# Ardev_version_3.net
KiCad netlist of a schematic drawn in EAGLE
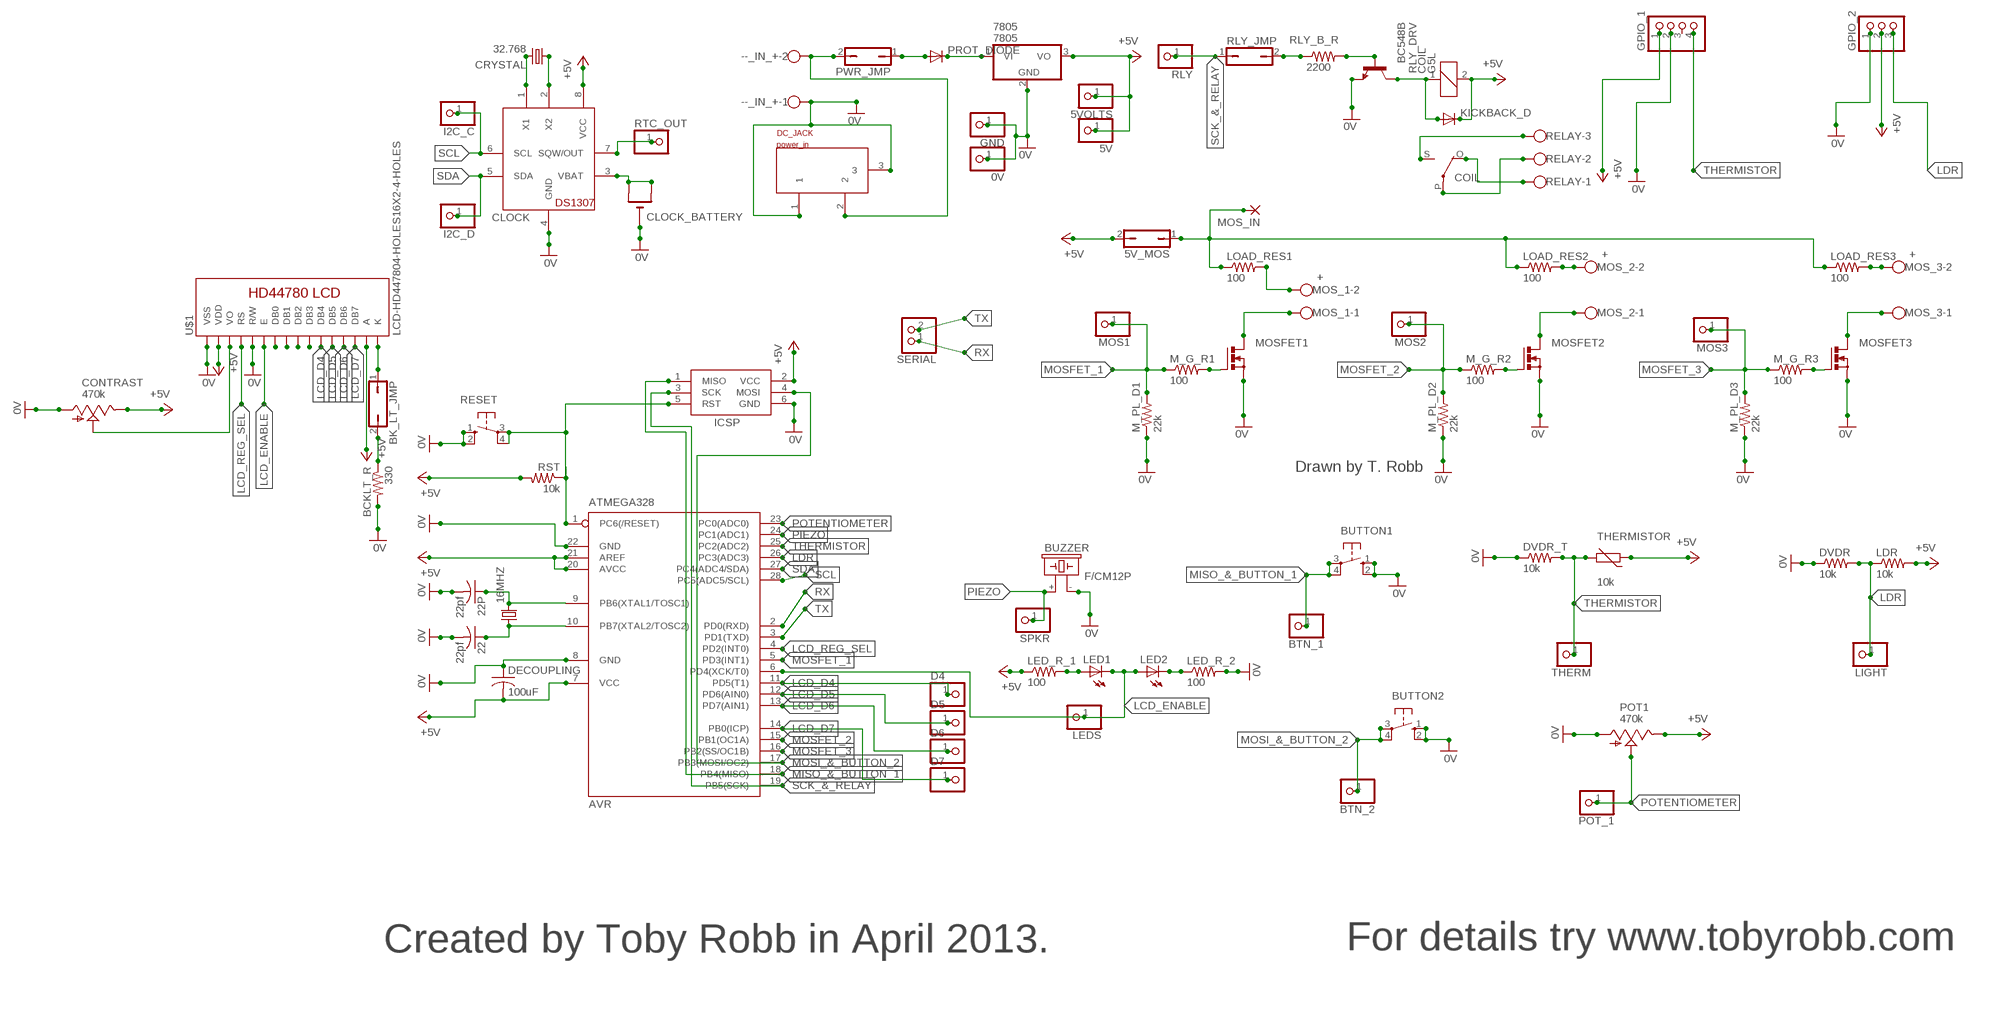
[diagram p0: schematic, sheet 1, part 1 of 2]
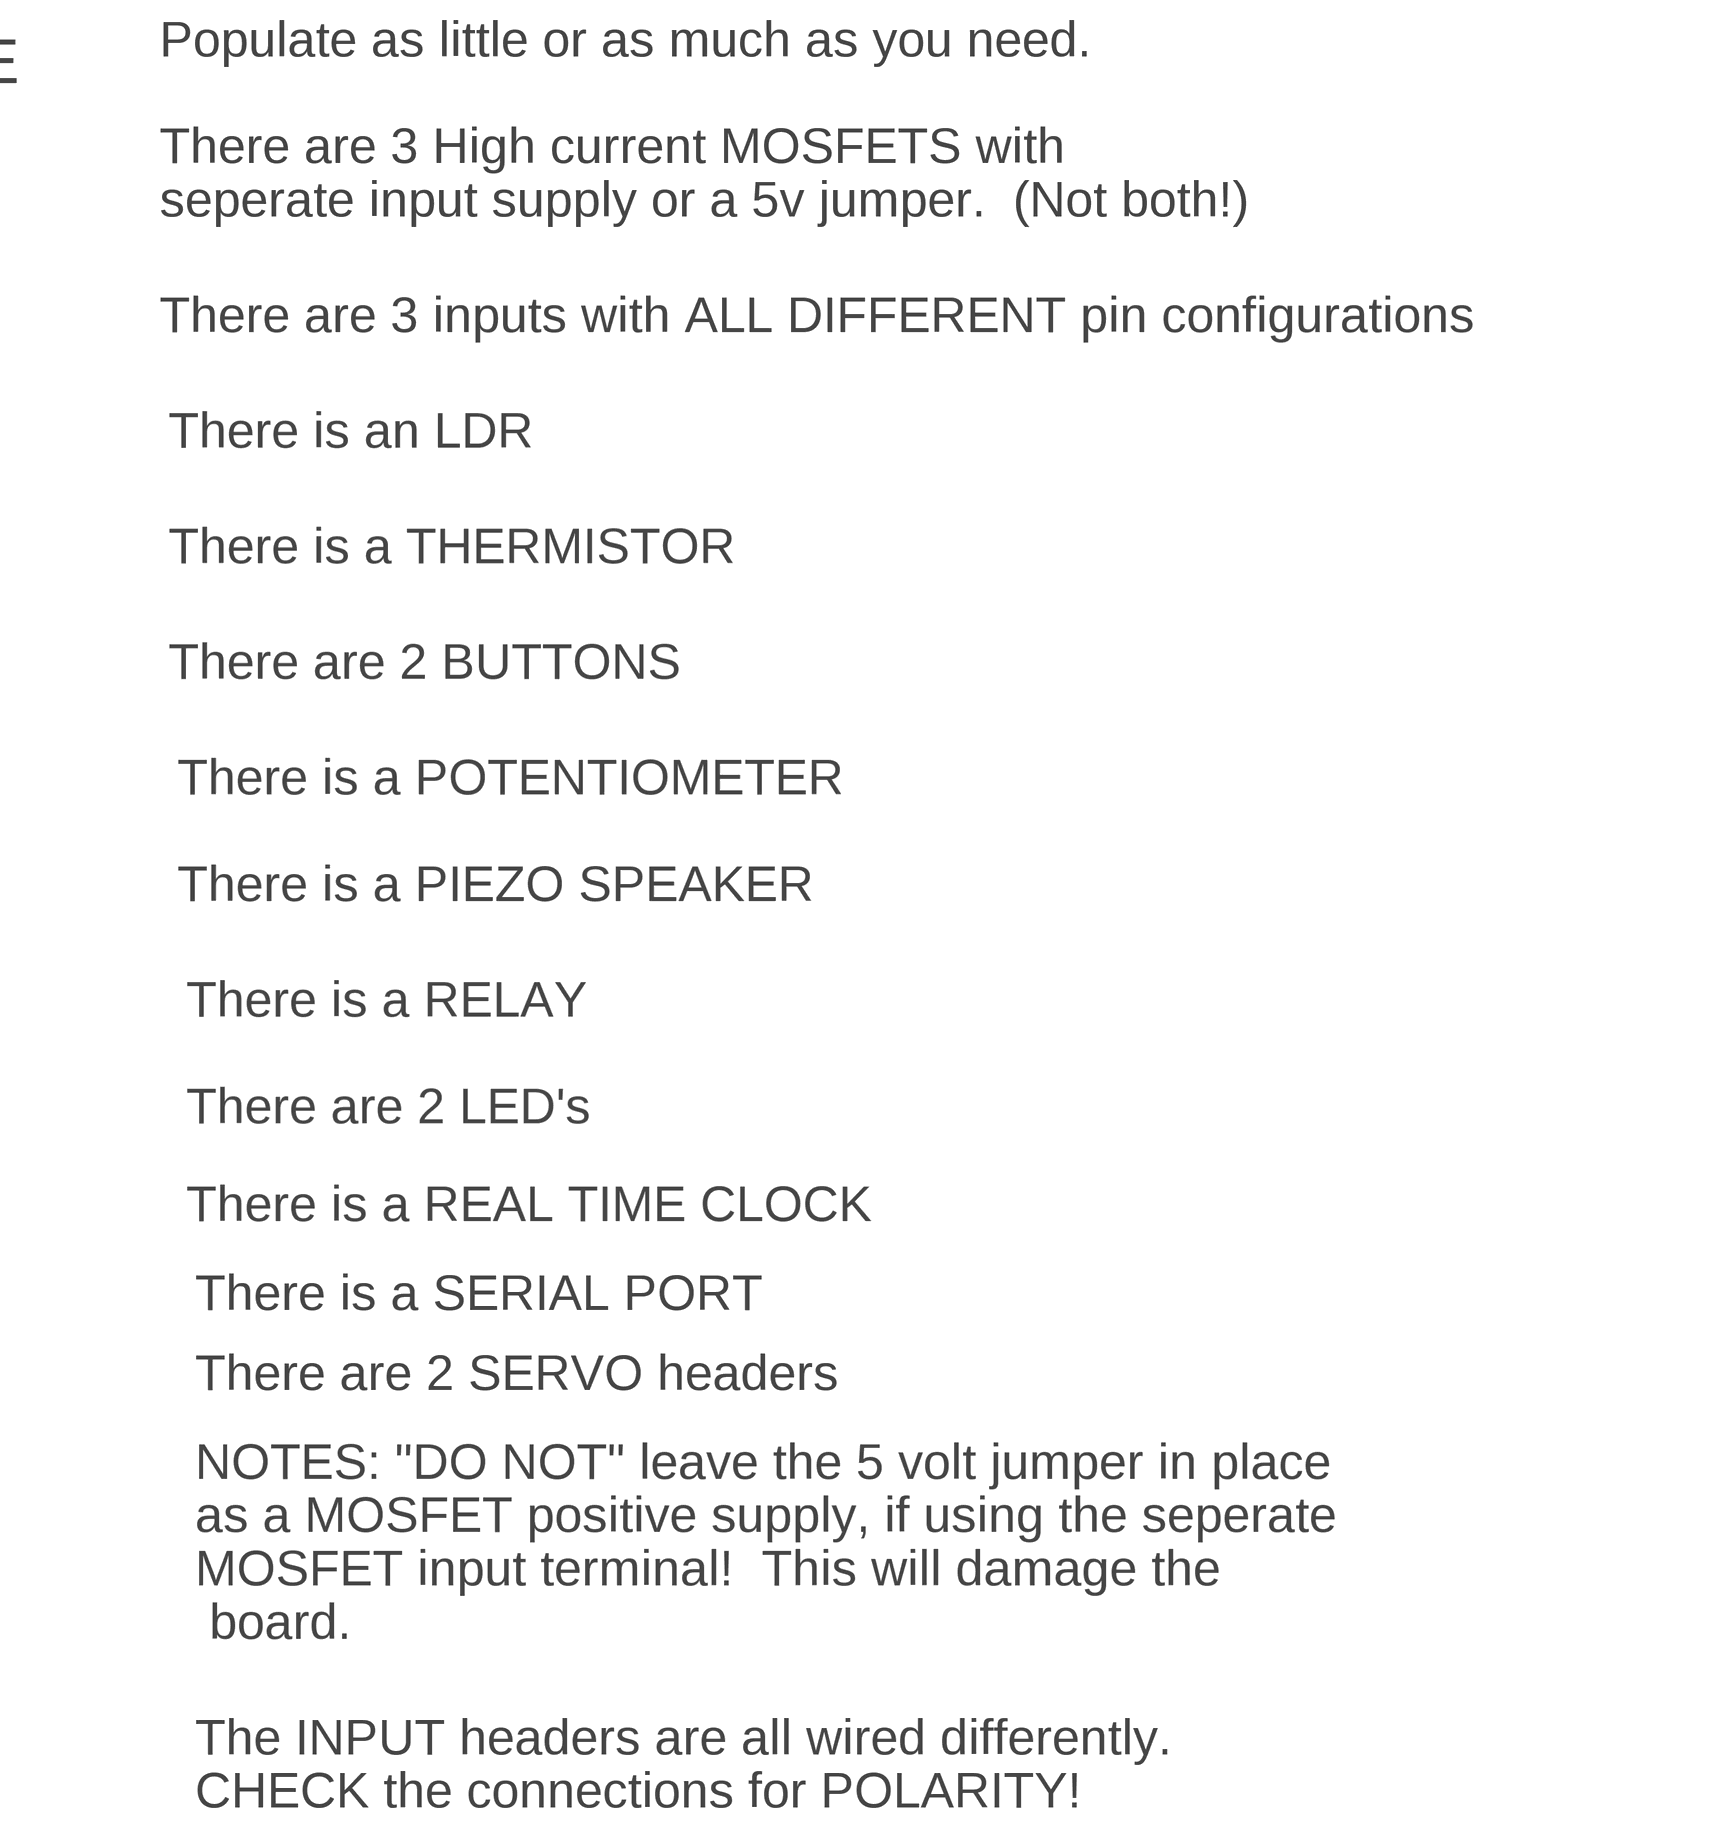
[diagram p1: schematic, sheet 1, part 2 of 2]

(export (version "E")
  (design (tool "Eeschema 10.0.6"))
  (components
    (comp (ref "--_IN_+")
      (value "W237-102")
      (footprint "eagle-import:W237-102")
      (fields (field (name "MPN") "237-102"))
      (libsource (lib "eagle-import") (part "W237-102"))
    )
    (comp (ref "0V")
      (value "PINHD-1X1")
      (footprint "eagle-import:1X01")
      (libsource (lib "eagle-import") (part "PINHD-1X1"))
    )
    (comp (ref "5V")
      (value "PINHD-1X1")
      (footprint "eagle-import:1X01")
      (libsource (lib "eagle-import") (part "PINHD-1X1"))
    )
    (comp (ref "5VOLTS")
      (value "PINHD-1X1")
      (footprint "eagle-import:1X01")
      (libsource (lib "eagle-import") (part "PINHD-1X1"))
    )
    (comp (ref "5V_MOS")
      (value "JP1Q")
      (footprint "eagle-import:JP1")
      (libsource (lib "eagle-import") (part "JP1Q"))
    )
    (comp (ref "16MHZ")
      (value "CRYSTALHC49U-V")
      (footprint "eagle-import:HC49U-V")
      (libsource (lib "eagle-import") (part "CRYSTALHC49U-V"))
    )
    (comp (ref "22")
      (value "22pf")
      (footprint "eagle-import:C025-050X050")
      (libsource (lib "eagle-import") (part "C-US025-050X050"))
    )
    (comp (ref "22P")
      (value "22pf")
      (footprint "eagle-import:C025-050X050")
      (libsource (lib "eagle-import") (part "C-US025-050X050"))
    )
    (comp (ref "7805")
      (value "7805")
      (footprint "eagle-import:TO220V")
      (libsource (lib "eagle-import") (part "78TV05"))
    )
    (comp (ref "AVR")
      (value "ATMEGA328")
      (footprint "eagle-import:DIL28-3")
      (libsource (lib "eagle-import") (part "MEGA8-P"))
    )
    (comp (ref "BCKLT_R")
      (value "330")
      (footprint "eagle-import:0309V")
      (libsource (lib "eagle-import") (part "R-US_0309/V"))
    )
    (comp (ref "BK_LT_JMP")
      (value "JP1Q")
      (footprint "eagle-import:JP1")
      (libsource (lib "eagle-import") (part "JP1Q"))
    )
    (comp (ref "BTN_1")
      (value "PINHD-1X1")
      (footprint "eagle-import:1X01")
      (libsource (lib "eagle-import") (part "PINHD-1X1"))
    )
    (comp (ref "BTN_2")
      (value "PINHD-1X1")
      (footprint "eagle-import:1X01")
      (libsource (lib "eagle-import") (part "PINHD-1X1"))
    )
    (comp (ref "BUTTON1")
      (value "10-XX")
      (footprint "eagle-import:B3F-10XX")
      (fields (field (name "MPN") "B3F-1000"))
      (libsource (lib "eagle-import") (part "10-XX"))
    )
    (comp (ref "BUTTON2")
      (value "10-XX")
      (footprint "eagle-import:B3F-10XX")
      (fields (field (name "MPN") "B3F-1000"))
      (libsource (lib "eagle-import") (part "10-XX"))
    )
    (comp (ref "BUZZER")
      (value "F/CM12P")
      (footprint "eagle-import:F_CM12P")
      (libsource (lib "eagle-import") (part "F/CM12P"))
    )
    (comp (ref "CLOCK")
      (value "DS1307")
      (footprint "eagle-import:DIL08")
      (libsource (lib "eagle-import") (part "DS1307"))
    )
    (comp (ref "CLOCK_BATTERY")
      (value "CR1220THM")
      (footprint "eagle-import:CR1220-THM")
      (libsource (lib "eagle-import") (part "CR1220THM"))
    )
    (comp (ref "COIL")
      (value "G5L")
      (footprint "eagle-import:G5LE")
      (libsource (lib "eagle-import") (part "G5L"))
    )
    (comp (ref "CONTRAST")
      (value "470k")
      (footprint "eagle-import:CA6V")
      (libsource (lib "eagle-import") (part "TRIM_US-CA6V"))
    )
    (comp (ref "CRYSTAL")
      (value "32.768")
      (footprint "eagle-import:TC26H")
      (libsource (lib "eagle-import") (part "CRYSTALTC26H"))
    )
    (comp (ref "D4")
      (value "PINHD-1X1")
      (footprint "eagle-import:1X01")
      (libsource (lib "eagle-import") (part "PINHD-1X1"))
    )
    (comp (ref "D5")
      (value "PINHD-1X1")
      (footprint "eagle-import:1X01")
      (libsource (lib "eagle-import") (part "PINHD-1X1"))
    )
    (comp (ref "D6")
      (value "PINHD-1X1")
      (footprint "eagle-import:1X01")
      (libsource (lib "eagle-import") (part "PINHD-1X1"))
    )
    (comp (ref "D7")
      (value "PINHD-1X1")
      (footprint "eagle-import:1X01")
      (libsource (lib "eagle-import") (part "PINHD-1X1"))
    )
    (comp (ref "DC_JACK")
      (value "power_in")
      (footprint "eagle-import:SMARTPRJ_POWERSUPPLY_DC-21MM")
      (libsource (lib "eagle-import") (part "SMARTPRJ_POWERSUPPLY_DC21MMX"))
    )
    (comp (ref "DECOUPLING")
      (value "100uF")
      (footprint "eagle-import:C025-050X050")
      (libsource (lib "eagle-import") (part "C-US025-050X050"))
    )
    (comp (ref "DVDR")
      (value "10k")
      (footprint "eagle-import:0309V")
      (libsource (lib "eagle-import") (part "R-US_0309/V"))
    )
    (comp (ref "DVDR_T")
      (value "10k")
      (footprint "eagle-import:0309V")
      (libsource (lib "eagle-import") (part "R-US_0309/V"))
    )
    (comp (ref "GND")
      (value "PINHD-1X1")
      (footprint "eagle-import:1X01")
      (libsource (lib "eagle-import") (part "PINHD-1X1"))
    )
    (comp (ref "GPIO_1")
      (value "PINHD-1X4")
      (footprint "eagle-import:1X04")
      (libsource (lib "eagle-import") (part "PINHD-1X4"))
    )
    (comp (ref "GPIO_2")
      (value "PINHD-1X3")
      (footprint "eagle-import:1X03")
      (libsource (lib "eagle-import") (part "PINHD-1X3"))
    )
    (comp (ref "I2C_C")
      (value "PINHD-1X1")
      (footprint "eagle-import:1X01")
      (libsource (lib "eagle-import") (part "PINHD-1X1"))
    )
    (comp (ref "I2C_D")
      (value "PINHD-1X1")
      (footprint "eagle-import:1X01")
      (libsource (lib "eagle-import") (part "PINHD-1X1"))
    )
    (comp (ref "ICSP")
      (value "AVRISP-6")
      (footprint "eagle-import:AVRISP")
      (libsource (lib "eagle-import") (part "AVRISP-6"))
    )
    (comp (ref "KICKBACK_D")
      (value "DIODE-D-7.5")
      (footprint "eagle-import:D-7.5")
      (libsource (lib "eagle-import") (part "DIODE-D-7.5"))
    )
    (comp (ref "LDR")
      (value "10k")
      (footprint "eagle-import:0309V")
      (libsource (lib "eagle-import") (part "R-US_0309/V"))
    )
    (comp (ref "LED1")
      (value "LED5MM")
      (footprint "eagle-import:LED5MM")
      (libsource (lib "eagle-import") (part "LED5MM"))
    )
    (comp (ref "LED2")
      (value "LED5MM")
      (footprint "eagle-import:LED5MM")
      (libsource (lib "eagle-import") (part "LED5MM"))
    )
    (comp (ref "LEDS")
      (value "PINHD-1X1")
      (footprint "eagle-import:1X01")
      (libsource (lib "eagle-import") (part "PINHD-1X1"))
    )
    (comp (ref "LED_R_1")
      (value "100")
      (footprint "eagle-import:0207_2V")
      (libsource (lib "eagle-import") (part "R-US_0207/2V"))
    )
    (comp (ref "LED_R_2")
      (value "100")
      (footprint "eagle-import:0207_2V")
      (libsource (lib "eagle-import") (part "R-US_0207/2V"))
    )
    (comp (ref "LIGHT")
      (value "PINHD-1X1")
      (footprint "eagle-import:1X01")
      (libsource (lib "eagle-import") (part "PINHD-1X1"))
    )
    (comp (ref "LOAD_RES1")
      (value "100")
      (footprint "eagle-import:0309V")
      (libsource (lib "eagle-import") (part "R-US_0309/V"))
    )
    (comp (ref "LOAD_RES2")
      (value "100")
      (footprint "eagle-import:0309V")
      (libsource (lib "eagle-import") (part "R-US_0309/V"))
    )
    (comp (ref "LOAD_RES3")
      (value "100")
      (footprint "eagle-import:0309V")
      (libsource (lib "eagle-import") (part "R-US_0309/V"))
    )
    (comp (ref "MOS1")
      (value "PINHD-1X1")
      (footprint "eagle-import:1X01")
      (libsource (lib "eagle-import") (part "PINHD-1X1"))
    )
    (comp (ref "MOS2")
      (value "PINHD-1X1")
      (footprint "eagle-import:1X01")
      (libsource (lib "eagle-import") (part "PINHD-1X1"))
    )
    (comp (ref "MOS3")
      (value "PINHD-1X1")
      (footprint "eagle-import:1X01")
      (libsource (lib "eagle-import") (part "PINHD-1X1"))
    )
    (comp (ref "MOSFET1")
      (value "IRF512")
      (footprint "eagle-import:TO220BV")
      (libsource (lib "eagle-import") (part "IRF512"))
    )
    (comp (ref "MOSFET2")
      (value "IRF512")
      (footprint "eagle-import:TO220BV")
      (libsource (lib "eagle-import") (part "IRF512"))
    )
    (comp (ref "MOSFET3")
      (value "IRF512")
      (footprint "eagle-import:TO220BV")
      (libsource (lib "eagle-import") (part "IRF512"))
    )
    (comp (ref "MOS_1")
      (value "+")
      (footprint "eagle-import:W237-102")
      (fields (field (name "MPN") "237-102"))
      (libsource (lib "eagle-import") (part "W237-102"))
    )
    (comp (ref "MOS_2")
      (value "+")
      (footprint "eagle-import:W237-102")
      (fields (field (name "MPN") "237-102"))
      (libsource (lib "eagle-import") (part "W237-102"))
    )
    (comp (ref "MOS_3")
      (value "+")
      (footprint "eagle-import:W237-102")
      (fields (field (name "MPN") "237-102"))
      (libsource (lib "eagle-import") (part "W237-102"))
    )
    (comp (ref "MOS_IN")
      (value "3,17/1,3")
      (footprint "eagle-import:3,17_1,3")
      (libsource (lib "eagle-import") (part "3,17/1,3"))
    )
    (comp (ref "M_G_R1")
      (value "100")
      (footprint "eagle-import:0309V")
      (libsource (lib "eagle-import") (part "R-US_0309/V"))
    )
    (comp (ref "M_G_R2")
      (value "100")
      (footprint "eagle-import:0309V")
      (libsource (lib "eagle-import") (part "R-US_0309/V"))
    )
    (comp (ref "M_G_R3")
      (value "100")
      (footprint "eagle-import:0309V")
      (libsource (lib "eagle-import") (part "R-US_0309/V"))
    )
    (comp (ref "M_PL_D1")
      (value "22k")
      (footprint "eagle-import:0309V")
      (libsource (lib "eagle-import") (part "R-US_0309/V"))
    )
    (comp (ref "M_PL_D2")
      (value "22k")
      (footprint "eagle-import:0309V")
      (libsource (lib "eagle-import") (part "R-US_0309/V"))
    )
    (comp (ref "M_PL_D3")
      (value "22k")
      (footprint "eagle-import:0309V")
      (libsource (lib "eagle-import") (part "R-US_0309/V"))
    )
    (comp (ref "POT1")
      (value "470k")
      (footprint "eagle-import:CA6V")
      (libsource (lib "eagle-import") (part "TRIM_US-CA6V"))
    )
    (comp (ref "POT_1")
      (value "PINHD-1X1")
      (footprint "eagle-import:1X01")
      (libsource (lib "eagle-import") (part "PINHD-1X1"))
    )
    (comp (ref "PROT_DIODE")
      (value "DIODE-D-7.5")
      (footprint "eagle-import:D-7.5")
      (libsource (lib "eagle-import") (part "DIODE-D-7.5"))
    )
    (comp (ref "PWR_JMP")
      (value "JP1Q")
      (footprint "eagle-import:JP1")
      (libsource (lib "eagle-import") (part "JP1Q"))
    )
    (comp (ref "RELAY")
      (value "W237-103")
      (footprint "eagle-import:W237-103")
      (fields (field (name "MPN") "237-103"))
      (libsource (lib "eagle-import") (part "W237-103"))
    )
    (comp (ref "RESET")
      (value "10-XX")
      (footprint "eagle-import:B3F-10XX")
      (fields (field (name "MPN") "B3F-1000"))
      (libsource (lib "eagle-import") (part "10-XX"))
    )
    (comp (ref "RLY")
      (value "PINHD-1X1")
      (footprint "eagle-import:1X01")
      (libsource (lib "eagle-import") (part "PINHD-1X1"))
    )
    (comp (ref "RLY_B_R")
      (value "2200")
      (footprint "eagle-import:0309V")
      (libsource (lib "eagle-import") (part "R-US_0309/V"))
    )
    (comp (ref "RLY_DRV")
      (value "BC548B")
      (footprint "eagle-import:TO92-EBC")
      (libsource (lib "eagle-import") (part "BC548B"))
    )
    (comp (ref "RLY_JMP")
      (value "JP1Q")
      (footprint "eagle-import:JP1")
      (libsource (lib "eagle-import") (part "JP1Q"))
    )
    (comp (ref "RST")
      (value "10k")
      (footprint "eagle-import:0309V")
      (libsource (lib "eagle-import") (part "R-US_0309/V"))
    )
    (comp (ref "RTC_OUT")
      (value "PINHD-1X1")
      (footprint "eagle-import:1X01")
      (libsource (lib "eagle-import") (part "PINHD-1X1"))
    )
    (comp (ref "SERIAL")
      (value "PINHD-1X2")
      (footprint "eagle-import:1X02")
      (libsource (lib "eagle-import") (part "PINHD-1X2"))
    )
    (comp (ref "SPKR")
      (value "PINHD-1X1")
      (footprint "eagle-import:1X01")
      (libsource (lib "eagle-import") (part "PINHD-1X1"))
    )
    (comp (ref "THERM")
      (value "PINHD-1X1")
      (footprint "eagle-import:1X01")
      (libsource (lib "eagle-import") (part "PINHD-1X1"))
    )
    (comp (ref "THERMISTOR")
      (value "10k")
      (footprint "eagle-import:RS-2,5")
      (libsource (lib "eagle-import") (part "THERMISTOR_R-2,5"))
    )
    (comp (ref "U$1")
      (value "LCD-HD447804-HOLES16X2-4-HOLES")
      (footprint "eagle-import:LCD-16X2-4HOLES")
      (libsource (lib "eagle-import") (part "LCD-HD4478016X2-4-HOLES4-HOLES"))
    )
  )
  (nets
    (net (code "1") (name "+5V") (class "Default")
      (node (ref "5V") (pin "1") (pinfunction "1_1") (pintype "passive"))
      (node (ref "5VOLTS") (pin "1") (pinfunction "1_1") (pintype "passive"))
      (node (ref "5V_MOS") (pin "2") (pinfunction "2_2") (pintype "passive"))
      (node (ref "7805") (pin "3") (pinfunction "VO_3") (pintype "passive"))
      (node (ref "AVR") (pin "20") (pinfunction "AVCC_20") (pintype "power_in"))
      (node (ref "AVR") (pin "21") (pinfunction "AREF_21") (pintype "passive"))
      (node (ref "AVR") (pin "7") (pinfunction "VCC_7") (pintype "power_in"))
      (node (ref "CLOCK") (pin "8") (pinfunction "VCC_8") (pintype "power_in"))
      (node (ref "COIL") (pin "2") (pinfunction "2_2") (pintype "passive"))
      (node (ref "CONTRAST") (pin "E") (pinfunction "E_E") (pintype "passive"))
      (node (ref "DECOUPLING") (pin "2") (pinfunction "2_2") (pintype "passive"))
      (node (ref "GPIO_1") (pin "1") (pinfunction "1_1") (pintype "passive"))
      (node (ref "GPIO_2") (pin "2") (pinfunction "2_2") (pintype "passive"))
      (node (ref "ICSP") (pin "2") (pinfunction "VCC_2") (pintype "power_in"))
      (node (ref "KICKBACK_D") (pin "C") (pinfunction "C_C") (pintype "passive"))
      (node (ref "LDR") (pin "2") (pinfunction "2_2") (pintype "passive"))
      (node (ref "LED_R_1") (pin "1") (pinfunction "1_1") (pintype "passive"))
      (node (ref "POT1") (pin "E") (pinfunction "E_E") (pintype "passive"))
      (node (ref "RST") (pin "2") (pinfunction "2_2") (pintype "passive"))
      (node (ref "THERMISTOR") (pin "1") (pinfunction "1_1") (pintype "passive"))
      (node (ref "U$1") (pin "15") (pinfunction "A_15") (pintype "power_in"))
      (node (ref "U$1") (pin "2") (pinfunction "VDD_2") (pintype "power_in"))
    )
    (net (code "2") (name "0V") (class "Default")
      (node (ref "--_IN_+") (pin "1") (pinfunction "KL_1") (pintype "passive"))
      (node (ref "0V") (pin "1") (pinfunction "1_1") (pintype "passive"))
      (node (ref "22") (pin "2") (pinfunction "2_2") (pintype "passive"))
      (node (ref "22P") (pin "2") (pinfunction "2_2") (pintype "passive"))
      (node (ref "7805") (pin "2") (pinfunction "GND_2") (pintype "passive"))
      (node (ref "AVR") (pin "22") (pinfunction "GND_22") (pintype "power_in"))
      (node (ref "AVR") (pin "8") (pinfunction "GND_8") (pintype "power_in"))
      (node (ref "BCKLT_R") (pin "2") (pinfunction "2_2") (pintype "passive"))
      (node (ref "BUTTON1") (pin "1") (pinfunction "S_1") (pintype "passive"))
      (node (ref "BUTTON1") (pin "2") (pinfunction "S1_2") (pintype "passive"))
      (node (ref "BUTTON2") (pin "1") (pinfunction "S_1") (pintype "passive"))
      (node (ref "BUTTON2") (pin "2") (pinfunction "S1_2") (pintype "passive"))
      (node (ref "BUZZER") (pin "-") (pinfunction "2_-") (pintype "passive"))
      (node (ref "CLOCK") (pin "4") (pinfunction "GND_4") (pintype "power_in"))
      (node (ref "CLOCK_BATTERY") (pin "-") (pinfunction "-_-") (pintype "passive"))
      (node (ref "CONTRAST") (pin "A") (pinfunction "A_A") (pintype "passive"))
      (node (ref "DC_JACK") (pin "1") (pinfunction "1_1") (pintype "power_in"))
      (node (ref "DC_JACK") (pin "3") (pinfunction "3_3") (pintype "power_in"))
      (node (ref "DECOUPLING") (pin "1") (pinfunction "1_1") (pintype "passive"))
      (node (ref "DVDR") (pin "1") (pinfunction "1_1") (pintype "passive"))
      (node (ref "DVDR_T") (pin "1") (pinfunction "1_1") (pintype "passive"))
      (node (ref "GND") (pin "1") (pinfunction "1_1") (pintype "passive"))
      (node (ref "GPIO_1") (pin "2") (pinfunction "2_2") (pintype "passive"))
      (node (ref "GPIO_2") (pin "1") (pinfunction "1_1") (pintype "passive"))
      (node (ref "ICSP") (pin "6") (pinfunction "GND_6") (pintype "power_in"))
      (node (ref "LED_R_2") (pin "2") (pinfunction "2_2") (pintype "passive"))
      (node (ref "MOSFET1") (pin "S") (pinfunction "S_S") (pintype "passive"))
      (node (ref "MOSFET2") (pin "S") (pinfunction "S_S") (pintype "passive"))
      (node (ref "MOSFET3") (pin "S") (pinfunction "S_S") (pintype "passive"))
      (node (ref "M_PL_D1") (pin "1") (pinfunction "1_1") (pintype "passive"))
      (node (ref "M_PL_D2") (pin "1") (pinfunction "1_1") (pintype "passive"))
      (node (ref "M_PL_D3") (pin "1") (pinfunction "1_1") (pintype "passive"))
      (node (ref "POT1") (pin "A") (pinfunction "A_A") (pintype "passive"))
      (node (ref "RESET") (pin "1") (pinfunction "S_1") (pintype "passive"))
      (node (ref "RESET") (pin "2") (pinfunction "S1_2") (pintype "passive"))
      (node (ref "RLY_DRV") (pin "E") (pinfunction "E_E") (pintype "passive"))
      (node (ref "U$1") (pin "1") (pinfunction "VSS_1") (pintype "power_in"))
      (node (ref "U$1") (pin "5") (pinfunction "R/W_5") (pintype "input"))
    )
    (net (code "3") (name "LCD_D4") (class "Default")
      (node (ref "AVR") (pin "11") (pinfunction "PD5(T1)_11") (pintype "bidirectional"))
      (node (ref "D4") (pin "1") (pinfunction "1_1") (pintype "passive"))
      (node (ref "U$1") (pin "11") (pinfunction "DB4_11") (pintype "bidirectional"))
    )
    (net (code "4") (name "LCD_D5") (class "Default")
      (node (ref "AVR") (pin "12") (pinfunction "PD6(AIN0)_12") (pintype "bidirectional"))
      (node (ref "D5") (pin "1") (pinfunction "1_1") (pintype "passive"))
      (node (ref "U$1") (pin "12") (pinfunction "DB5_12") (pintype "bidirectional"))
    )
    (net (code "5") (name "LCD_D6") (class "Default")
      (node (ref "AVR") (pin "13") (pinfunction "PD7(AIN1)_13") (pintype "bidirectional"))
      (node (ref "D6") (pin "1") (pinfunction "1_1") (pintype "passive"))
      (node (ref "U$1") (pin "13") (pinfunction "DB6_13") (pintype "bidirectional"))
    )
    (net (code "6") (name "LCD_D7") (class "Default")
      (node (ref "AVR") (pin "14") (pinfunction "PB0(ICP)_14") (pintype "bidirectional"))
      (node (ref "D7") (pin "1") (pinfunction "1_1") (pintype "passive"))
      (node (ref "U$1") (pin "14") (pinfunction "DB7_14") (pintype "bidirectional"))
    )
    (net (code "7") (name "LCD_ENABLE") (class "Default")
      (node (ref "AVR") (pin "6") (pinfunction "PD4(XCK/T0)_6") (pintype "bidirectional"))
      (node (ref "LED1") (pin "K") (pinfunction "C_K") (pintype "passive"))
      (node (ref "LED2") (pin "A") (pinfunction "A_A") (pintype "passive"))
      (node (ref "LEDS") (pin "1") (pinfunction "1_1") (pintype "passive"))
      (node (ref "U$1") (pin "6") (pinfunction "E_6") (pintype "input"))
    )
    (net (code "8") (name "LCD_REG_SEL") (class "Default")
      (node (ref "AVR") (pin "4") (pinfunction "PD2(INT0)_4") (pintype "bidirectional"))
      (node (ref "U$1") (pin "4") (pinfunction "RS_4") (pintype "input"))
    )
    (net (code "9") (name "LDR") (class "Default")
      (node (ref "AVR") (pin "26") (pinfunction "PC3(ADC3)_26") (pintype "bidirectional"))
      (node (ref "DVDR") (pin "2") (pinfunction "2_2") (pintype "passive"))
      (node (ref "GPIO_2") (pin "3") (pinfunction "3_3") (pintype "passive"))
      (node (ref "LDR") (pin "1") (pinfunction "1_1") (pintype "passive"))
      (node (ref "LIGHT") (pin "1") (pinfunction "1_1") (pintype "passive"))
    )
    (net (code "10") (name "MISO_&_BUTTON_1") (class "Default")
      (node (ref "AVR") (pin "18") (pinfunction "PB4(MISO)_18") (pintype "bidirectional"))
      (node (ref "BTN_1") (pin "1") (pinfunction "1_1") (pintype "passive"))
      (node (ref "BUTTON1") (pin "3") (pinfunction "P_3") (pintype "passive"))
      (node (ref "BUTTON1") (pin "4") (pinfunction "P1_4") (pintype "passive"))
      (node (ref "ICSP") (pin "1") (pinfunction "MISO_1") (pintype "input"))
    )
    (net (code "11") (name "MOSFET_1") (class "Default")
      (node (ref "AVR") (pin "5") (pinfunction "PD3(INT1)_5") (pintype "bidirectional"))
      (node (ref "MOS1") (pin "1") (pinfunction "1_1") (pintype "passive"))
      (node (ref "M_G_R1") (pin "1") (pinfunction "1_1") (pintype "passive"))
      (node (ref "M_PL_D1") (pin "2") (pinfunction "2_2") (pintype "passive"))
    )
    (net (code "12") (name "MOSFET_2") (class "Default")
      (node (ref "AVR") (pin "15") (pinfunction "PB1(OC1A)_15") (pintype "bidirectional"))
      (node (ref "MOS2") (pin "1") (pinfunction "1_1") (pintype "passive"))
      (node (ref "M_G_R2") (pin "1") (pinfunction "1_1") (pintype "passive"))
      (node (ref "M_PL_D2") (pin "2") (pinfunction "2_2") (pintype "passive"))
    )
    (net (code "13") (name "MOSFET_3") (class "Default")
      (node (ref "AVR") (pin "16") (pinfunction "PB2(SS/OC1B)_16") (pintype "bidirectional"))
      (node (ref "MOS3") (pin "1") (pinfunction "1_1") (pintype "passive"))
      (node (ref "M_G_R3") (pin "1") (pinfunction "1_1") (pintype "passive"))
      (node (ref "M_PL_D3") (pin "2") (pinfunction "2_2") (pintype "passive"))
    )
    (net (code "14") (name "MOSI_&_BUTTON_2") (class "Default")
      (node (ref "AVR") (pin "17") (pinfunction "PB3(MOSI/OC2)_17") (pintype "bidirectional"))
      (node (ref "BTN_2") (pin "1") (pinfunction "1_1") (pintype "passive"))
      (node (ref "BUTTON2") (pin "3") (pinfunction "P_3") (pintype "passive"))
      (node (ref "BUTTON2") (pin "4") (pinfunction "P1_4") (pintype "passive"))
      (node (ref "ICSP") (pin "4") (pinfunction "MOSI_4") (pintype "output"))
    )
    (net (code "15") (name "Net-(--_IN_+B-KL)") (class "Default")
      (node (ref "--_IN_+") (pin "2") (pinfunction "KL_2") (pintype "passive"))
      (node (ref "DC_JACK") (pin "2") (pinfunction "2_2") (pintype "power_in"))
      (node (ref "PWR_JMP") (pin "2") (pinfunction "2_2") (pintype "passive"))
    )
    (net (code "16") (name "Net-(7805-VI)") (class "Default")
      (node (ref "7805") (pin "1") (pinfunction "VI_1") (pintype "input"))
      (node (ref "PROT_DIODE") (pin "C") (pinfunction "C_C") (pintype "passive"))
    )
    (net (code "17") (name "Net-(AVR-PB6(XTAL1{slash}TOSC1))") (class "Default")
      (node (ref "16MHZ") (pin "2") (pinfunction "2_2") (pintype "passive"))
      (node (ref "22P") (pin "1") (pinfunction "1_1") (pintype "passive"))
      (node (ref "AVR") (pin "9") (pinfunction "PB6(XTAL1/TOSC1)_9") (pintype "bidirectional"))
    )
    (net (code "18") (name "Net-(AVR-PB7(XTAL2{slash}TOSC2))") (class "Default")
      (node (ref "16MHZ") (pin "1") (pinfunction "1_1") (pintype "passive"))
      (node (ref "22") (pin "1") (pinfunction "1_1") (pintype "passive"))
      (node (ref "AVR") (pin "10") (pinfunction "PB7(XTAL2/TOSC2)_10") (pintype "bidirectional"))
    )
    (net (code "19") (name "Net-(AVR-PC6({slash}RESET))") (class "Default")
      (node (ref "AVR") (pin "1") (pinfunction "PC6(/RESET)_1") (pintype "bidirectional"))
      (node (ref "ICSP") (pin "5") (pinfunction "RST_5") (pintype "output"))
      (node (ref "RESET") (pin "3") (pinfunction "P_3") (pintype "passive"))
      (node (ref "RESET") (pin "4") (pinfunction "P1_4") (pintype "passive"))
      (node (ref "RST") (pin "1") (pinfunction "1_1") (pintype "passive"))
    )
    (net (code "20") (name "Net-(BCKLT_R-Pad1)") (class "Default")
      (node (ref "BCKLT_R") (pin "1") (pinfunction "1_1") (pintype "passive"))
      (node (ref "BK_LT_JMP") (pin "2") (pinfunction "2_2") (pintype "passive"))
    )
    (net (code "21") (name "Net-(CLOCK-SQW{slash}OUT)") (class "Default")
      (node (ref "CLOCK") (pin "7") (pinfunction "SQW/OUT_7") (pintype "bidirectional"))
      (node (ref "RTC_OUT") (pin "1") (pinfunction "1_1") (pintype "passive"))
    )
    (net (code "22") (name "Net-(CLOCK-VBAT)") (class "Default")
      (node (ref "CLOCK") (pin "3") (pinfunction "VBAT_3") (pintype "power_in"))
      (node (ref "CLOCK_BATTERY") (pin "+1") (pinfunction "+_+1") (pintype "passive"))
      (node (ref "CLOCK_BATTERY") (pin "+2") (pinfunction "+1_+2") (pintype "passive"))
    )
    (net (code "23") (name "Net-(CLOCK-X1)") (class "Default")
      (node (ref "CLOCK") (pin "1") (pinfunction "X1_1") (pintype "passive"))
      (node (ref "CRYSTAL") (pin "2") (pinfunction "2_2") (pintype "passive"))
    )
    (net (code "24") (name "Net-(CLOCK-X2)") (class "Default")
      (node (ref "CLOCK") (pin "2") (pinfunction "X2_2") (pintype "passive"))
      (node (ref "CRYSTAL") (pin "1") (pinfunction "1_1") (pintype "passive"))
    )
    (net (code "25") (name "Net-(COIL-Pad1)") (class "Default")
      (node (ref "COIL") (pin "1") (pinfunction "1_1") (pintype "passive"))
      (node (ref "KICKBACK_D") (pin "A") (pinfunction "A_A") (pintype "passive"))
      (node (ref "RLY_DRV") (pin "C") (pinfunction "C_C") (pintype "passive"))
    )
    (net (code "26") (name "Net-(LED1-PadA)") (class "Default")
      (node (ref "LED1") (pin "A") (pinfunction "A_A") (pintype "passive"))
      (node (ref "LED_R_1") (pin "2") (pinfunction "2_2") (pintype "passive"))
    )
    (net (code "27") (name "Net-(LED2-C)") (class "Default")
      (node (ref "LED2") (pin "K") (pinfunction "C_K") (pintype "passive"))
      (node (ref "LED_R_2") (pin "1") (pinfunction "1_1") (pintype "passive"))
    )
    (net (code "28") (name "Net-(MOSFET1-PadG)") (class "Default")
      (node (ref "MOSFET1") (pin "G") (pinfunction "G_G") (pintype "passive"))
      (node (ref "M_G_R1") (pin "2") (pinfunction "2_2") (pintype "passive"))
    )
    (net (code "29") (name "Net-(MOSFET2-PadG)") (class "Default")
      (node (ref "MOSFET2") (pin "G") (pinfunction "G_G") (pintype "passive"))
      (node (ref "M_G_R2") (pin "2") (pinfunction "2_2") (pintype "passive"))
    )
    (net (code "30") (name "Net-(MOSFET3-PadG)") (class "Default")
      (node (ref "MOSFET3") (pin "G") (pinfunction "G_G") (pintype "passive"))
      (node (ref "M_G_R3") (pin "2") (pinfunction "2_2") (pintype "passive"))
    )
    (net (code "31") (name "Net-(MOS_1A-KL)") (class "Default")
      (node (ref "MOSFET1") (pin "D") (pinfunction "D_D") (pintype "passive"))
      (node (ref "MOS_1") (pin "1") (pinfunction "KL_1") (pintype "passive"))
    )
    (net (code "32") (name "Net-(MOS_1B-KL)") (class "Default")
      (node (ref "LOAD_RES1") (pin "2") (pinfunction "2_2") (pintype "passive"))
      (node (ref "MOS_1") (pin "2") (pinfunction "KL_2") (pintype "passive"))
    )
    (net (code "33") (name "Net-(MOS_2A-KL)") (class "Default")
      (node (ref "MOSFET2") (pin "D") (pinfunction "D_D") (pintype "passive"))
      (node (ref "MOS_2") (pin "1") (pinfunction "KL_1") (pintype "passive"))
    )
    (net (code "34") (name "Net-(MOS_2B-KL)") (class "Default")
      (node (ref "LOAD_RES2") (pin "2") (pinfunction "2_2") (pintype "passive"))
      (node (ref "MOS_2") (pin "2") (pinfunction "KL_2") (pintype "passive"))
    )
    (net (code "35") (name "Net-(MOS_3A-KL)") (class "Default")
      (node (ref "MOSFET3") (pin "D") (pinfunction "D_D") (pintype "passive"))
      (node (ref "MOS_3") (pin "1") (pinfunction "KL_1") (pintype "passive"))
    )
    (net (code "36") (name "Net-(MOS_3B-KL)") (class "Default")
      (node (ref "LOAD_RES3") (pin "2") (pinfunction "2_2") (pintype "passive"))
      (node (ref "MOS_3") (pin "2") (pinfunction "KL_2") (pintype "passive"))
    )
    (net (code "37") (name "Net-(MOS_IN-P)") (class "Default")
      (node (ref "5V_MOS") (pin "1") (pinfunction "1_1") (pintype "passive"))
      (node (ref "LOAD_RES1") (pin "1") (pinfunction "1_1") (pintype "passive"))
      (node (ref "LOAD_RES2") (pin "1") (pinfunction "1_1") (pintype "passive"))
      (node (ref "LOAD_RES3") (pin "1") (pinfunction "1_1") (pintype "passive"))
      (node (ref "MOS_IN") (pin "1") (pinfunction "P_1") (pintype "passive"))
    )
    (net (code "38") (name "Net-(PROT_DIODE-PadA)") (class "Default")
      (node (ref "PROT_DIODE") (pin "A") (pinfunction "A_A") (pintype "passive"))
      (node (ref "PWR_JMP") (pin "1") (pinfunction "1_1") (pintype "passive"))
    )
    (net (code "39") (name "Net-(RELAYA-KL)") (class "Default")
      (node (ref "COIL") (pin "O") (pinfunction "O_O") (pintype "passive"))
      (node (ref "RELAY") (pin "1") (pinfunction "KL_1") (pintype "passive"))
    )
    (net (code "40") (name "Net-(RELAYB-KL)") (class "Default")
      (node (ref "COIL") (pin "P") (pinfunction "P_P") (pintype "passive"))
      (node (ref "RELAY") (pin "2") (pinfunction "KL_2") (pintype "passive"))
    )
    (net (code "41") (name "Net-(RELAYC-KL)") (class "Default")
      (node (ref "COIL") (pin "S") (pinfunction "S_S") (pintype "passive"))
      (node (ref "RELAY") (pin "3") (pinfunction "KL_3") (pintype "passive"))
    )
    (net (code "42") (name "Net-(RLY_B_R-Pad1)") (class "Default")
      (node (ref "RLY_B_R") (pin "1") (pinfunction "1_1") (pintype "passive"))
      (node (ref "RLY_JMP") (pin "2") (pinfunction "2_2") (pintype "passive"))
    )
    (net (code "43") (name "Net-(RLY_B_R-Pad2)") (class "Default")
      (node (ref "RLY_B_R") (pin "2") (pinfunction "2_2") (pintype "passive"))
      (node (ref "RLY_DRV") (pin "B") (pinfunction "B_B") (pintype "passive"))
    )
    (net (code "44") (name "Net-(U$1-K)") (class "Default")
      (node (ref "BK_LT_JMP") (pin "1") (pinfunction "1_1") (pintype "passive"))
      (node (ref "U$1") (pin "16") (pinfunction "K_16") (pintype "power_in"))
    )
    (net (code "45") (name "Net-(U$1-VO)") (class "Default")
      (node (ref "CONTRAST") (pin "S") (pinfunction "S_S") (pintype "passive"))
      (node (ref "U$1") (pin "3") (pinfunction "VO_3") (pintype "bidirectional"))
    )
    (net (code "46") (name "PIEZO") (class "Default")
      (node (ref "AVR") (pin "24") (pinfunction "PC1(ADC1)_24") (pintype "bidirectional"))
      (node (ref "BUZZER") (pin "+") (pinfunction "1_+") (pintype "passive"))
      (node (ref "SPKR") (pin "1") (pinfunction "1_1") (pintype "passive"))
    )
    (net (code "47") (name "POTENTIOMETER") (class "Default")
      (node (ref "AVR") (pin "23") (pinfunction "PC0(ADC0)_23") (pintype "bidirectional"))
      (node (ref "POT1") (pin "S") (pinfunction "S_S") (pintype "passive"))
      (node (ref "POT_1") (pin "1") (pinfunction "1_1") (pintype "passive"))
    )
    (net (code "48") (name "RX") (class "Default")
      (node (ref "AVR") (pin "2") (pinfunction "PD0(RXD)_2") (pintype "bidirectional"))
      (node (ref "SERIAL") (pin "1") (pinfunction "1_1") (pintype "passive"))
    )
    (net (code "49") (name "SCK_&_RELAY") (class "Default")
      (node (ref "AVR") (pin "19") (pinfunction "PB5(SCK)_19") (pintype "bidirectional"))
      (node (ref "ICSP") (pin "3") (pinfunction "SCK_3") (pintype "output"))
      (node (ref "RLY") (pin "1") (pinfunction "1_1") (pintype "passive"))
      (node (ref "RLY_JMP") (pin "1") (pinfunction "1_1") (pintype "passive"))
    )
    (net (code "50") (name "SCL") (class "Default")
      (node (ref "AVR") (pin "28") (pinfunction "PC5(ADC5/SCL)_28") (pintype "bidirectional"))
      (node (ref "CLOCK") (pin "6") (pinfunction "SCL_6") (pintype "bidirectional"))
      (node (ref "I2C_C") (pin "1") (pinfunction "1_1") (pintype "passive"))
    )
    (net (code "51") (name "SDA") (class "Default")
      (node (ref "AVR") (pin "27") (pinfunction "PC4(ADC4/SDA)_27") (pintype "bidirectional"))
      (node (ref "CLOCK") (pin "5") (pinfunction "SDA_5") (pintype "bidirectional"))
      (node (ref "I2C_D") (pin "1") (pinfunction "1_1") (pintype "passive"))
    )
    (net (code "52") (name "THERMISTOR") (class "Default")
      (node (ref "AVR") (pin "25") (pinfunction "PC2(ADC2)_25") (pintype "bidirectional"))
      (node (ref "DVDR_T") (pin "2") (pinfunction "2_2") (pintype "passive"))
      (node (ref "GPIO_1") (pin "4") (pinfunction "4_4") (pintype "passive"))
      (node (ref "THERM") (pin "1") (pinfunction "1_1") (pintype "passive"))
      (node (ref "THERMISTOR") (pin "2") (pinfunction "2_2") (pintype "passive"))
    )
    (net (code "53") (name "TX") (class "Default")
      (node (ref "AVR") (pin "3") (pinfunction "PD1(TXD)_3") (pintype "bidirectional"))
      (node (ref "SERIAL") (pin "2") (pinfunction "2_2") (pintype "passive"))
    )
    (net (code "54") (name "unconnected-(GPIO_1-Pad3)") (class "Default")
      (node (ref "GPIO_1") (pin "3") (pinfunction "3_3") (pintype "passive"))
    )
    (net (code "55") (name "unconnected-(U$1-DB0-Pad7)") (class "Default")
      (node (ref "U$1") (pin "7") (pinfunction "DB0_7") (pintype "bidirectional"))
    )
    (net (code "56") (name "unconnected-(U$1-DB1-Pad8)") (class "Default")
      (node (ref "U$1") (pin "8") (pinfunction "DB1_8") (pintype "bidirectional"))
    )
    (net (code "57") (name "unconnected-(U$1-DB2-Pad9)") (class "Default")
      (node (ref "U$1") (pin "9") (pinfunction "DB2_9") (pintype "bidirectional"))
    )
    (net (code "58") (name "unconnected-(U$1-DB3-Pad10)") (class "Default")
      (node (ref "U$1") (pin "10") (pinfunction "DB3_10") (pintype "bidirectional"))
    )
  )
)
